# pmic_bq25690_battcharger.net
KiCad netlist of a schematic drawn in Altium Designer
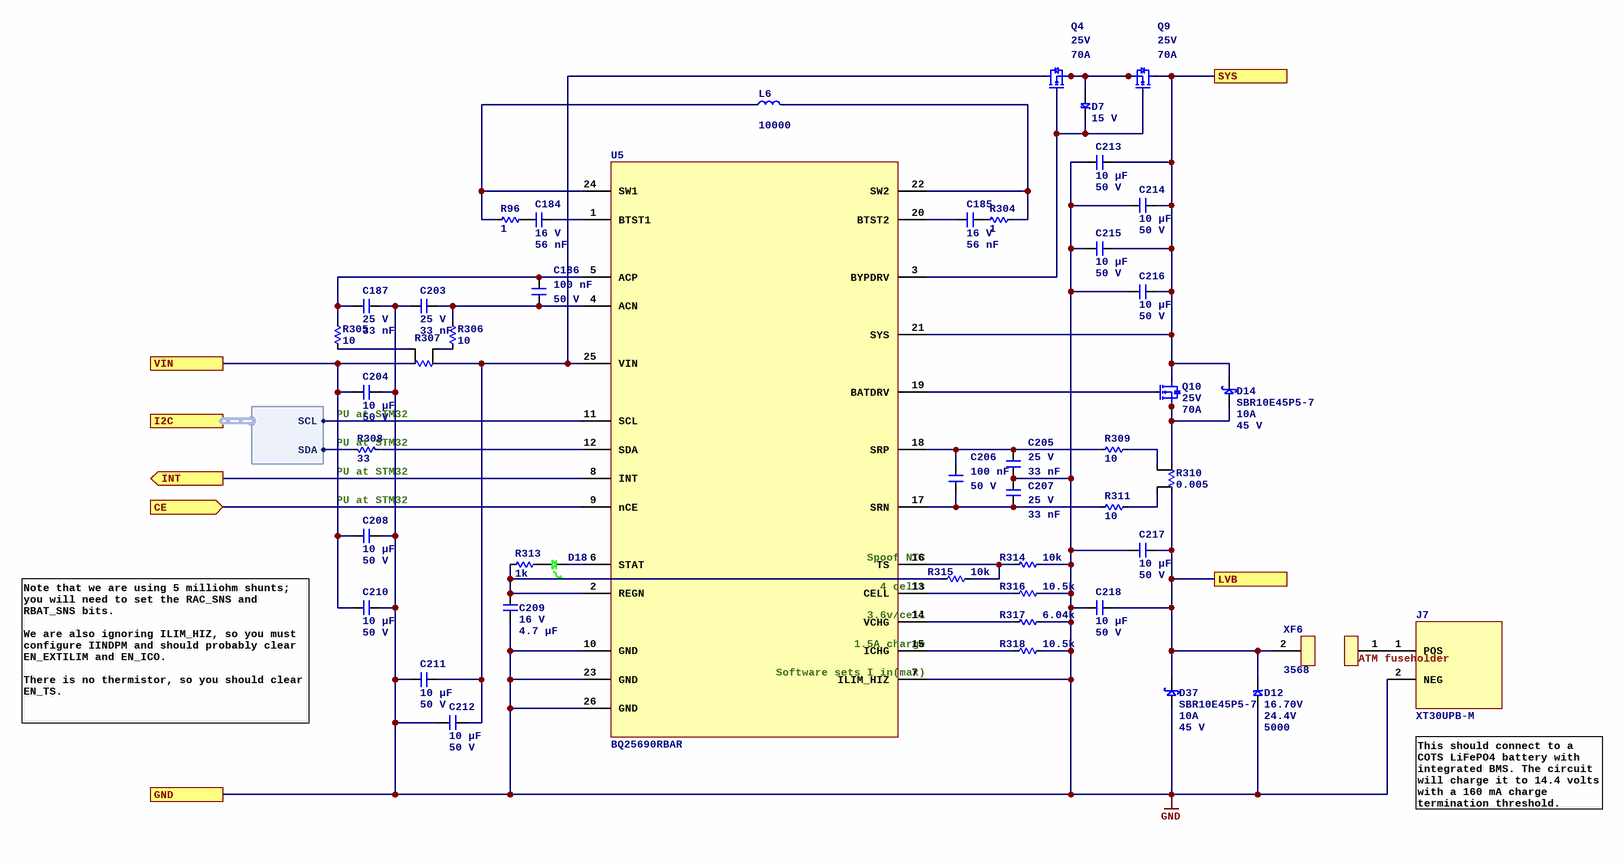
[diagram p0: pmic_bq25690_battcharger.SchDoc]

(export (version "E")
  (design (tool "Eeschema 10.0.6"))
  (components
    (comp (ref "C184")
      (value "CC0402KRX7R7BB563")
      (footprint "C0402")
      (fields
        (field (name "MANUFACTURER") "YAGEO")
        (field (name "VOLTAGE RATING") "16 V")
        (field (name "CAPACITANCE") "56 nF")
      )
      (libsource (lib "database") (part "__template_cap"))
    )
    (comp (ref "C185")
      (value "CC0402KRX7R7BB563")
      (footprint "C0402")
      (fields
        (field (name "MANUFACTURER") "YAGEO")
        (field (name "VOLTAGE RATING") "16 V")
        (field (name "CAPACITANCE") "56 nF")
      )
      (libsource (lib "database") (part "__template_cap"))
    )
    (comp (ref "C186")
      (value "CL05B104KB54PNC")
      (footprint "C0402")
      (fields
        (field (name "CAPACITANCE") "100 nF")
        (field (name "MANUFACTURER") "Samsung Electro-Mechanics")
        (field (name "VOLTAGE RATING") "50 V")
      )
      (libsource (lib "database") (part "__template_cap"))
    )
    (comp (ref "C187")
      (value "0402B333K250NT")
      (footprint "C0402")
      (fields
        (field (name "MANUFACTURER") "FH (Guangdong Fenghua Advanced Tech)")
        (field (name "VOLTAGE RATING") "25 V")
        (field (name "CAPACITANCE") "33 nF")
      )
      (libsource (lib "database") (part "__template_cap"))
    )
    (comp (ref "C203")
      (value "0402B333K250NT")
      (footprint "C0402")
      (fields
        (field (name "MANUFACTURER") "FH (Guangdong Fenghua Advanced Tech)")
        (field (name "VOLTAGE RATING") "25 V")
        (field (name "CAPACITANCE") "33 nF")
      )
      (libsource (lib "database") (part "__template_cap"))
    )
    (comp (ref "C204")
      (value "CL31B106KBHNNNE")
      (footprint "C1206")
      (fields
        (field (name "CAPACITANCE") "10 µF")
        (field (name "MANUFACTURER") "Samsung Electro-Mechanics")
        (field (name "VOLTAGE RATING") "50 V")
      )
      (libsource (lib "database") (part "__template_cap"))
    )
    (comp (ref "C205")
      (value "0402B333K250NT")
      (footprint "C0402")
      (fields
        (field (name "MANUFACTURER") "FH (Guangdong Fenghua Advanced Tech)")
        (field (name "VOLTAGE RATING") "25 V")
        (field (name "CAPACITANCE") "33 nF")
      )
      (libsource (lib "database") (part "__template_cap"))
    )
    (comp (ref "C206")
      (value "CL05B104KB54PNC")
      (footprint "C0402")
      (fields
        (field (name "CAPACITANCE") "100 nF")
        (field (name "MANUFACTURER") "Samsung Electro-Mechanics")
        (field (name "VOLTAGE RATING") "50 V")
      )
      (libsource (lib "database") (part "__template_cap"))
    )
    (comp (ref "C207")
      (value "0402B333K250NT")
      (footprint "C0402")
      (fields
        (field (name "MANUFACTURER") "FH (Guangdong Fenghua Advanced Tech)")
        (field (name "VOLTAGE RATING") "25 V")
        (field (name "CAPACITANCE") "33 nF")
      )
      (libsource (lib "database") (part "__template_cap"))
    )
    (comp (ref "C208")
      (value "CL31B106KBHNNNE")
      (footprint "C1206")
      (fields
        (field (name "CAPACITANCE") "10 µF")
        (field (name "MANUFACTURER") "Samsung Electro-Mechanics")
        (field (name "VOLTAGE RATING") "50 V")
      )
      (libsource (lib "database") (part "__template_cap"))
    )
    (comp (ref "C209")
      (value "GRM188Z71C475KE21D")
      (footprint "C0603")
      (fields
        (field (name "MANUFACTURER") "Murata Electronics")
        (field (name "VOLTAGE RATING") "16 V")
        (field (name "CAPACITANCE") "4.7 µF")
      )
      (libsource (lib "database") (part "__template_cap"))
    )
    (comp (ref "C210")
      (value "CL31B106KBHNNNE")
      (footprint "C1206")
      (fields
        (field (name "CAPACITANCE") "10 µF")
        (field (name "MANUFACTURER") "Samsung Electro-Mechanics")
        (field (name "VOLTAGE RATING") "50 V")
      )
      (libsource (lib "database") (part "__template_cap"))
    )
    (comp (ref "C211")
      (value "CL31B106KBHNNNE")
      (footprint "C1206")
      (fields
        (field (name "CAPACITANCE") "10 µF")
        (field (name "MANUFACTURER") "Samsung Electro-Mechanics")
        (field (name "VOLTAGE RATING") "50 V")
      )
      (libsource (lib "database") (part "__template_cap"))
    )
    (comp (ref "C212")
      (value "CL31B106KBHNNNE")
      (footprint "C1206")
      (fields
        (field (name "CAPACITANCE") "10 µF")
        (field (name "MANUFACTURER") "Samsung Electro-Mechanics")
        (field (name "VOLTAGE RATING") "50 V")
      )
      (libsource (lib "database") (part "__template_cap"))
    )
    (comp (ref "C213")
      (value "CL31B106KBHNNNE")
      (footprint "C1206")
      (fields
        (field (name "CAPACITANCE") "10 µF")
        (field (name "MANUFACTURER") "Samsung Electro-Mechanics")
        (field (name "VOLTAGE RATING") "50 V")
      )
      (libsource (lib "database") (part "__template_cap"))
    )
    (comp (ref "C214")
      (value "CL31B106KBHNNNE")
      (footprint "C1206")
      (fields
        (field (name "CAPACITANCE") "10 µF")
        (field (name "MANUFACTURER") "Samsung Electro-Mechanics")
        (field (name "VOLTAGE RATING") "50 V")
      )
      (libsource (lib "database") (part "__template_cap"))
    )
    (comp (ref "C215")
      (value "CL31B106KBHNNNE")
      (footprint "C1206")
      (fields
        (field (name "CAPACITANCE") "10 µF")
        (field (name "MANUFACTURER") "Samsung Electro-Mechanics")
        (field (name "VOLTAGE RATING") "50 V")
      )
      (libsource (lib "database") (part "__template_cap"))
    )
    (comp (ref "C216")
      (value "CL31B106KBHNNNE")
      (footprint "C1206")
      (fields
        (field (name "CAPACITANCE") "10 µF")
        (field (name "MANUFACTURER") "Samsung Electro-Mechanics")
        (field (name "VOLTAGE RATING") "50 V")
      )
      (libsource (lib "database") (part "__template_cap"))
    )
    (comp (ref "C217")
      (value "CL31B106KBHNNNE")
      (footprint "C1206")
      (fields
        (field (name "CAPACITANCE") "10 µF")
        (field (name "MANUFACTURER") "Samsung Electro-Mechanics")
        (field (name "VOLTAGE RATING") "50 V")
      )
      (libsource (lib "database") (part "__template_cap"))
    )
    (comp (ref "C218")
      (value "CL31B106KBHNNNE")
      (footprint "C1206")
      (fields
        (field (name "CAPACITANCE") "10 µF")
        (field (name "MANUFACTURER") "Samsung Electro-Mechanics")
        (field (name "VOLTAGE RATING") "50 V")
      )
      (libsource (lib "database") (part "__template_cap"))
    )
    (comp (ref "D7")
      (value "MM3Z15VC")
      (footprint "SOD323")
      (description "DIODE ZENER 15V 200MW SOD")
      (fields (field (name "MANUFACTURER") "onsemi") (field (name "VR") "15 V"))
      (libsource (lib "database") (part "__template_diode_zener"))
    )
    (comp (ref "D12")
      (value "5.0SMDJ15A")
      (footprint "SMC")
      (description "TVS DIODE 15VWM 24.4VC DO214AB")
      (fields
        (field (name "MANUFACTURER") "Bourns Inc.")
        (field (name "MIN BREAKDOWN VOLTAGE") "16.70V")
        (field (name "CLAMPING VOLTAGE-MAX") "24.4V")
        (field (name "POWER (W)") "5000")
      )
      (libsource (lib "database") (part "__template_diode_tvs_uni"))
    )
    (comp (ref "D14")
      (value "SBR10E45P5-7")
      (footprint "POWERDI5")
      (description "Rectifier Diode, 1 Phase, 1 Element, 10A, 45V V(RRM), Silicon")
      (fields
        (field (name "MANUFACTURER") "Diodes")
        (field (name "CURRENT") "10A")
        (field (name "VR") "45 V")
      )
      (libsource (lib "database") (part "__template_diode_schottky"))
    )
    (comp (ref "D18")
      (value "LTST-C190GKT")
      (footprint "LED_0603P_GREEN")
      (description "LED GREEN CLEAR 0603 SMD")
      (fields (field (name "MANUFACTURER") "Lite-On Inc"))
      (libsource (lib "database") (part "__template_led_green"))
    )
    (comp (ref "D37")
      (value "SBR10E45P5-7")
      (footprint "POWERDI5")
      (description "Rectifier Diode, 1 Phase, 1 Element, 10A, 45V V(RRM), Silicon")
      (fields
        (field (name "MANUFACTURER") "Diodes")
        (field (name "CURRENT") "10A")
        (field (name "VR") "45 V")
      )
      (libsource (lib "database") (part "__template_diode_schottky"))
    )
    (comp (ref "J7")
      (value "XT30UPB-M")
      (footprint "AMASS_XT30UPB-M")
      (description "Vertical PCB mount XT30 male")
      (fields (field (name "MANUFACTURER") "Changzhou Amass Elec"))
      (libsource (lib "database") (part "XT30UPB-M"))
    )
    (comp (ref "L6")
      (value "SRP1265A-100M")
      (footprint "BOURNS_SRP1265A")
      (description "10 µH shielded power inductor")
      (fields (field (name "MANUFACTURER") "BOURNS") (field (name "CURRENT RATING (MA)") "10000"))
      (libsource (lib "database") (part "__template_inductor"))
    )
    (comp (ref "Q4")
      (value "PSMN2R0-25MLDX")
      (footprint "SOT1210")
      (description "N-Channel 25 V 70A (Tc) 74W (Tc) Surface Mount LFPAK33")
      (fields
        (field (name "MANUFACTURER") "Nexperia")
        (field (name "VOLTAGE") "25V")
        (field (name "CURRENT") "70A")
      )
      (libsource (lib "database") (part "PSMN2R0-25MLDX"))
    )
    (comp (ref "Q9")
      (value "PSMN2R0-25MLDX")
      (footprint "SOT1210")
      (description "N-Channel 25 V 70A (Tc) 74W (Tc) Surface Mount LFPAK33")
      (fields
        (field (name "MANUFACTURER") "Nexperia")
        (field (name "VOLTAGE") "25V")
        (field (name "CURRENT") "70A")
      )
      (libsource (lib "database") (part "PSMN2R0-25MLDX"))
    )
    (comp (ref "Q10")
      (value "PSMN2R0-25MLDX")
      (footprint "SOT1210")
      (description "N-Channel 25 V 70A (Tc) 74W (Tc) Surface Mount LFPAK33")
      (fields
        (field (name "MANUFACTURER") "Nexperia")
        (field (name "VOLTAGE") "25V")
        (field (name "CURRENT") "70A")
      )
      (libsource (lib "database") (part "PSMN2R0-25MLDX"))
    )
    (comp (ref "R96")
      (value "1")
      (footprint "R0402")
      (fields
        (field (name "MANUFACTURER PART NUMBER") "CRCW04021R00FKED")
        (field (name "MANUFACTURER") "Vishay Intertech")
        (field (name "TOLERANCE") "1%")
      )
      (libsource (lib "database") (part "__template_resistor"))
    )
    (comp (ref "R304")
      (value "1")
      (footprint "R0402")
      (fields
        (field (name "MANUFACTURER PART NUMBER") "CRCW04021R00FKED")
        (field (name "MANUFACTURER") "Vishay Intertech")
        (field (name "TOLERANCE") "1%")
      )
      (libsource (lib "database") (part "__template_resistor"))
    )
    (comp (ref "R305")
      (value "10")
      (footprint "R0402")
      (fields
        (field (name "MANUFACTURER PART NUMBER") "FRC0402F10R0TS")
        (field (name "MANUFACTURER") "FOJAN")
        (field (name "TOLERANCE") "1%")
      )
      (libsource (lib "database") (part "__template_resistor"))
    )
    (comp (ref "R306")
      (value "10")
      (footprint "R0402")
      (fields
        (field (name "MANUFACTURER PART NUMBER") "FRC0402F10R0TS")
        (field (name "MANUFACTURER") "FOJAN")
        (field (name "TOLERANCE") "1%")
      )
      (libsource (lib "database") (part "__template_resistor"))
    )
    (comp (ref "R307")
      (value "WSL27265L000FEB")
      (footprint "VISHAY_WSL2726")
      (fields (field (name "MANUFACTURER") "Vishay Dale") (field (name "TOLERANCE") "1%"))
      (libsource (lib "database") (part "__template_shunt"))
    )
    (comp (ref "R308")
      (value "33")
      (footprint "R0402")
      (fields
        (field (name "TOLERANCE") "1%")
        (field (name "MANUFACTURER PART NUMBER") "0402WGF330JTCE")
        (field (name "MANUFACTURER") "UNI-ROYAL(Uniroyal Elec)")
      )
      (libsource (lib "database") (part "__template_resistor"))
    )
    (comp (ref "R309")
      (value "10")
      (footprint "R0402")
      (fields
        (field (name "MANUFACTURER PART NUMBER") "FRC0402F10R0TS")
        (field (name "MANUFACTURER") "FOJAN")
        (field (name "TOLERANCE") "1%")
      )
      (libsource (lib "database") (part "__template_resistor"))
    )
    (comp (ref "R310")
      (value "0.005")
      (footprint "VISHAY_WSL2726")
      (fields
        (field (name "MANUFACTURER") "Vishay Dale")
        (field (name "MANUFACTURER PART NUMBER") "WSL27265L000FEB")
        (field (name "TOLERANCE") "1%")
      )
      (libsource (lib "database") (part "__template_shunt"))
    )
    (comp (ref "R311")
      (value "10")
      (footprint "R0402")
      (fields
        (field (name "MANUFACTURER PART NUMBER") "FRC0402F10R0TS")
        (field (name "MANUFACTURER") "FOJAN")
        (field (name "TOLERANCE") "1%")
      )
      (libsource (lib "database") (part "__template_resistor"))
    )
    (comp (ref "R313")
      (value "1k")
      (footprint "R0402")
      (fields
        (field (name "TOLERANCE") "1%")
        (field (name "MANUFACTURER PART NUMBER") "0402WGF1001TCE")
        (field (name "MANUFACTURER") "UNI-ROYAL(Uniroyal Elec)")
      )
      (libsource (lib "database") (part "__template_resistor"))
    )
    (comp (ref "R314")
      (value "10k")
      (footprint "R0402")
      (fields
        (field (name "MANUFACTURER PART NUMBER") "0402WGF1002TCE")
        (field (name "MANUFACTURER") "UNI-ROYAL(Uniroyal Elec)")
        (field (name "TOLERANCE") "1%")
      )
      (libsource (lib "database") (part "__template_resistor"))
    )
    (comp (ref "R315")
      (value "10k")
      (footprint "R0402")
      (fields
        (field (name "MANUFACTURER PART NUMBER") "0402WGF1002TCE")
        (field (name "MANUFACTURER") "UNI-ROYAL(Uniroyal Elec)")
        (field (name "TOLERANCE") "1%")
      )
      (libsource (lib "database") (part "__template_resistor"))
    )
    (comp (ref "R316")
      (value "10.5k")
      (footprint "R0402")
      (fields
        (field (name "MANUFACTURER PART NUMBER") "0402WGF1052TCE")
        (field (name "MANUFACTURER") "UNI-ROYAL(Uniroyal Elec)")
        (field (name "TOLERANCE") "1%")
      )
      (libsource (lib "database") (part "__template_resistor"))
    )
    (comp (ref "R317")
      (value "6.04k")
      (footprint "R0402")
      (fields
        (field (name "MANUFACTURER PART NUMBER") "0402WGF6041TCE")
        (field (name "MANUFACTURER") "UNI-ROYAL(Uniroyal Elec)")
        (field (name "TOLERANCE") "1%")
      )
      (libsource (lib "database") (part "__template_resistor"))
    )
    (comp (ref "R318")
      (value "10.5k")
      (footprint "R0402")
      (fields
        (field (name "MANUFACTURER PART NUMBER") "0402WGF1052TCE")
        (field (name "MANUFACTURER") "UNI-ROYAL(Uniroyal Elec)")
        (field (name "TOLERANCE") "1%")
      )
      (libsource (lib "database") (part "__template_resistor"))
    )
    (comp (ref "U5")
      (value "BQ25690RBAR")
      (footprint "TI_RBA")
      (description "Charger IC Lithium Ion/Polymer 26-WQFN-HR (4x3.5)")
      (fields (field (name "MANUFACTURER") "Texas Instruments"))
      (libsource (lib "database") (part "BQ25690RBAR"))
    )
    (comp (ref "XF6")
      (value "3568")
      (footprint "FUSEHOLDER_KEYSTONE_3568")
      (description "Fuse Holder 30 A 500V 1 Circuit Blade Through Hole")
      (fields (field (name "MANUFACTURER") "Keystone Electronics"))
      (libsource (lib "database") (part "3568"))
    )
  )
  (nets
    (net (code "2") (name "/CE") (class "Default")
      (node (ref "U5") (pin "9") (pinfunction "nCE_9") (pintype "passive"))
    )
    (net (code "3") (name "/INT") (class "Default")
      (node (ref "U5") (pin "8") (pinfunction "INT_8") (pintype "passive"))
    )
    (net (code "4") (name "/LVB") (class "Default")
      (node (ref "C217") (pin "1") (pintype "passive"))
      (node (ref "C218") (pin "1") (pintype "passive"))
      (node (ref "D12") (pin "2") (pintype "passive"))
      (node (ref "D37") (pin "2") (pintype "passive"))
      (node (ref "R310") (pin "2") (pintype "passive"))
      (node (ref "XF6") (pin "2") (pintype "passive"))
    )
    (net (code "5") (name "/SCL") (class "Default")
      (node (ref "U5") (pin "11") (pinfunction "SCL_11") (pintype "passive"))
    )
    (net (code "6") (name "/SDA") (class "Default") (node (ref "R308") (pin "1") (pintype "passive")))
    (net (code "7") (name "/SYS") (class "Default")
      (node (ref "C213") (pin "1") (pintype "passive"))
      (node (ref "C214") (pin "1") (pintype "passive"))
      (node (ref "C215") (pin "1") (pintype "passive"))
      (node (ref "C216") (pin "1") (pintype "passive"))
      (node (ref "D14") (pin "2") (pintype "passive"))
      (node (ref "Q10") (pin "5") (pintype "passive"))
      (node (ref "Q9") (pin "5") (pintype "passive"))
      (node (ref "U5") (pin "21") (pinfunction "SYS_21") (pintype "passive"))
    )
    (net (code "8") (name "/VIN") (class "Default")
      (node (ref "C204") (pin "1") (pintype "passive"))
      (node (ref "C208") (pin "1") (pintype "passive"))
      (node (ref "C210") (pin "1") (pintype "passive"))
      (node (ref "R307") (pin "2") (pintype "passive"))
    )
    (net (code "10") (name "GND") (class "Default")
      (node (ref "C187") (pin "2") (pintype "passive"))
      (node (ref "C203") (pin "1") (pintype "passive"))
      (node (ref "C204") (pin "2") (pintype "passive"))
      (node (ref "C205") (pin "1") (pintype "passive"))
      (node (ref "C207") (pin "2") (pintype "passive"))
      (node (ref "C208") (pin "2") (pintype "passive"))
      (node (ref "C209") (pin "1") (pintype "passive"))
      (node (ref "C210") (pin "2") (pintype "passive"))
      (node (ref "C211") (pin "2") (pintype "passive"))
      (node (ref "C212") (pin "2") (pintype "passive"))
      (node (ref "C213") (pin "2") (pintype "passive"))
      (node (ref "C214") (pin "2") (pintype "passive"))
      (node (ref "C215") (pin "2") (pintype "passive"))
      (node (ref "C216") (pin "2") (pintype "passive"))
      (node (ref "C217") (pin "2") (pintype "passive"))
      (node (ref "C218") (pin "2") (pintype "passive"))
      (node (ref "D12") (pin "1") (pintype "passive"))
      (node (ref "D37") (pin "1") (pintype "passive"))
      (node (ref "J7") (pin "2") (pinfunction "NEG_2") (pintype "passive"))
      (node (ref "R314") (pin "1") (pintype "passive"))
      (node (ref "R316") (pin "1") (pintype "passive"))
      (node (ref "R317") (pin "1") (pintype "passive"))
      (node (ref "R318") (pin "1") (pintype "passive"))
      (node (ref "U5") (pin "10") (pinfunction "GND_10") (pintype "passive"))
      (node (ref "U5") (pin "23") (pinfunction "GND_23") (pintype "passive"))
      (node (ref "U5") (pin "26") (pinfunction "GND_26") (pintype "passive"))
      (node (ref "U5") (pin "7") (pinfunction "ILIM_HIZ_7") (pintype "passive"))
    )
    (net (code "11") (name "Net-(C184-Pad1)") (class "Default")
      (node (ref "C184") (pin "1") (pintype "passive"))
      (node (ref "R96") (pin "2") (pintype "passive"))
    )
    (net (code "12") (name "Net-(C185-Pad2)") (class "Default")
      (node (ref "C185") (pin "2") (pintype "passive"))
      (node (ref "R304") (pin "1") (pintype "passive"))
    )
    (net (code "13") (name "Net-(D7-Pad1)") (class "Default")
      (node (ref "D7") (pin "1") (pintype "passive"))
      (node (ref "Q4") (pin "1") (pintype "passive"))
      (node (ref "Q4") (pin "2") (pintype "passive"))
      (node (ref "Q4") (pin "3") (pintype "passive"))
      (node (ref "Q9") (pin "1") (pintype "passive"))
      (node (ref "Q9") (pin "2") (pintype "passive"))
      (node (ref "Q9") (pin "3") (pintype "passive"))
    )
    (net (code "14") (name "Net-(D14-Pad1)") (class "Default")
      (node (ref "D14") (pin "1") (pintype "passive"))
      (node (ref "Q10") (pin "1") (pintype "passive"))
      (node (ref "Q10") (pin "2") (pintype "passive"))
      (node (ref "Q10") (pin "3") (pintype "passive"))
      (node (ref "R310") (pin "1") (pintype "passive"))
    )
    (net (code "15") (name "Net-(D18-Pad1)") (class "Default")
      (node (ref "D18") (pin "1") (pintype "passive"))
      (node (ref "R313") (pin "2") (pintype "passive"))
    )
    (net (code "16") (name "Net-(J7-POS)") (class "Default")
      (node (ref "J7") (pin "1") (pinfunction "POS_1") (pintype "passive"))
      (node (ref "XF6") (pin "1") (pintype "passive"))
    )
    (net (code "17") (name "Net-(R305-Pad1)") (class "Default")
      (node (ref "R305") (pin "1") (pintype "passive"))
      (node (ref "R307") (pin "4") (pintype "passive"))
    )
    (net (code "18") (name "Net-(R306-Pad1)") (class "Default")
      (node (ref "R306") (pin "1") (pintype "passive"))
      (node (ref "R307") (pin "3") (pintype "passive"))
    )
    (net (code "19") (name "Net-(R309-Pad1)") (class "Default")
      (node (ref "R309") (pin "1") (pintype "passive"))
      (node (ref "R310") (pin "3") (pintype "passive"))
    )
    (net (code "20") (name "Net-(R310-Pad4)") (class "Default")
      (node (ref "R310") (pin "4") (pintype "passive"))
      (node (ref "R311") (pin "1") (pintype "passive"))
    )
    (net (code "21") (name "Net-(U5-ACN)") (class "Default")
      (node (ref "C186") (pin "2") (pintype "passive"))
      (node (ref "C203") (pin "2") (pintype "passive"))
      (node (ref "R306") (pin "2") (pintype "passive"))
      (node (ref "U5") (pin "4") (pinfunction "ACN_4") (pintype "passive"))
    )
    (net (code "22") (name "Net-(U5-ACP)") (class "Default")
      (node (ref "C186") (pin "1") (pintype "passive"))
      (node (ref "C187") (pin "1") (pintype "passive"))
      (node (ref "R305") (pin "2") (pintype "passive"))
      (node (ref "U5") (pin "5") (pinfunction "ACP_5") (pintype "passive"))
    )
    (net (code "23") (name "Net-(U5-BATDRV)") (class "Default")
      (node (ref "Q10") (pin "4") (pintype "passive"))
      (node (ref "U5") (pin "19") (pinfunction "BATDRV_19") (pintype "passive"))
    )
    (net (code "24") (name "Net-(U5-BTST1)") (class "Default")
      (node (ref "C184") (pin "2") (pintype "passive"))
      (node (ref "U5") (pin "1") (pinfunction "BTST1_1") (pintype "passive"))
    )
    (net (code "25") (name "Net-(U5-BTST2)") (class "Default")
      (node (ref "C185") (pin "1") (pintype "passive"))
      (node (ref "U5") (pin "20") (pinfunction "BTST2_20") (pintype "passive"))
    )
    (net (code "26") (name "Net-(U5-BYPDRV)") (class "Default")
      (node (ref "D7") (pin "2") (pintype "passive"))
      (node (ref "Q4") (pin "4") (pintype "passive"))
      (node (ref "Q9") (pin "4") (pintype "passive"))
      (node (ref "U5") (pin "3") (pinfunction "BYPDRV_3") (pintype "passive"))
    )
    (net (code "27") (name "Net-(U5-CELL)") (class "Default")
      (node (ref "R316") (pin "2") (pintype "passive"))
      (node (ref "U5") (pin "13") (pinfunction "CELL_13") (pintype "passive"))
    )
    (net (code "28") (name "Net-(U5-ICHG)") (class "Default")
      (node (ref "R318") (pin "2") (pintype "passive"))
      (node (ref "U5") (pin "15") (pinfunction "ICHG_15") (pintype "passive"))
    )
    (net (code "29") (name "Net-(U5-REGN)") (class "Default")
      (node (ref "C209") (pin "2") (pintype "passive"))
      (node (ref "R313") (pin "1") (pintype "passive"))
      (node (ref "R315") (pin "2") (pintype "passive"))
      (node (ref "U5") (pin "2") (pinfunction "REGN_2") (pintype "passive"))
    )
    (net (code "30") (name "Net-(U5-SDA)") (class "Default")
      (node (ref "R308") (pin "2") (pintype "passive"))
      (node (ref "U5") (pin "12") (pinfunction "SDA_12") (pintype "passive"))
    )
    (net (code "31") (name "Net-(U5-SRN)") (class "Default")
      (node (ref "C206") (pin "2") (pintype "passive"))
      (node (ref "C207") (pin "1") (pintype "passive"))
      (node (ref "R311") (pin "2") (pintype "passive"))
      (node (ref "U5") (pin "17") (pinfunction "SRN_17") (pintype "passive"))
    )
    (net (code "32") (name "Net-(U5-SRP)") (class "Default")
      (node (ref "C205") (pin "2") (pintype "passive"))
      (node (ref "C206") (pin "1") (pintype "passive"))
      (node (ref "R309") (pin "2") (pintype "passive"))
      (node (ref "U5") (pin "18") (pinfunction "SRP_18") (pintype "passive"))
    )
    (net (code "33") (name "Net-(U5-STAT)") (class "Default")
      (node (ref "D18") (pin "2") (pintype "passive"))
      (node (ref "U5") (pin "6") (pinfunction "STAT_6") (pintype "passive"))
    )
    (net (code "34") (name "Net-(U5-SW1)") (class "Default")
      (node (ref "L6") (pin "1") (pintype "passive"))
      (node (ref "R96") (pin "1") (pintype "passive"))
      (node (ref "U5") (pin "24") (pinfunction "SW1_24") (pintype "passive"))
    )
    (net (code "35") (name "Net-(U5-SW2)") (class "Default")
      (node (ref "L6") (pin "2") (pintype "passive"))
      (node (ref "R304") (pin "2") (pintype "passive"))
      (node (ref "U5") (pin "22") (pinfunction "SW2_22") (pintype "passive"))
    )
    (net (code "36") (name "Net-(U5-TS)") (class "Default")
      (node (ref "R314") (pin "2") (pintype "passive"))
      (node (ref "R315") (pin "1") (pintype "passive"))
      (node (ref "U5") (pin "16") (pinfunction "TS_16") (pintype "passive"))
    )
    (net (code "37") (name "Net-(U5-VCHG)") (class "Default")
      (node (ref "R317") (pin "2") (pintype "passive"))
      (node (ref "U5") (pin "14") (pinfunction "VCHG_14") (pintype "passive"))
    )
    (net (code "38") (name "Net-(U5-VIN)") (class "Default")
      (node (ref "C211") (pin "1") (pintype "passive"))
      (node (ref "C212") (pin "1") (pintype "passive"))
      (node (ref "Q4") (pin "5") (pintype "passive"))
      (node (ref "R307") (pin "1") (pintype "passive"))
      (node (ref "U5") (pin "25") (pinfunction "VIN_25") (pintype "passive"))
    )
  )
)
